# sherlock_anderson.net
KiCad netlist of a schematic drawn in EAGLE
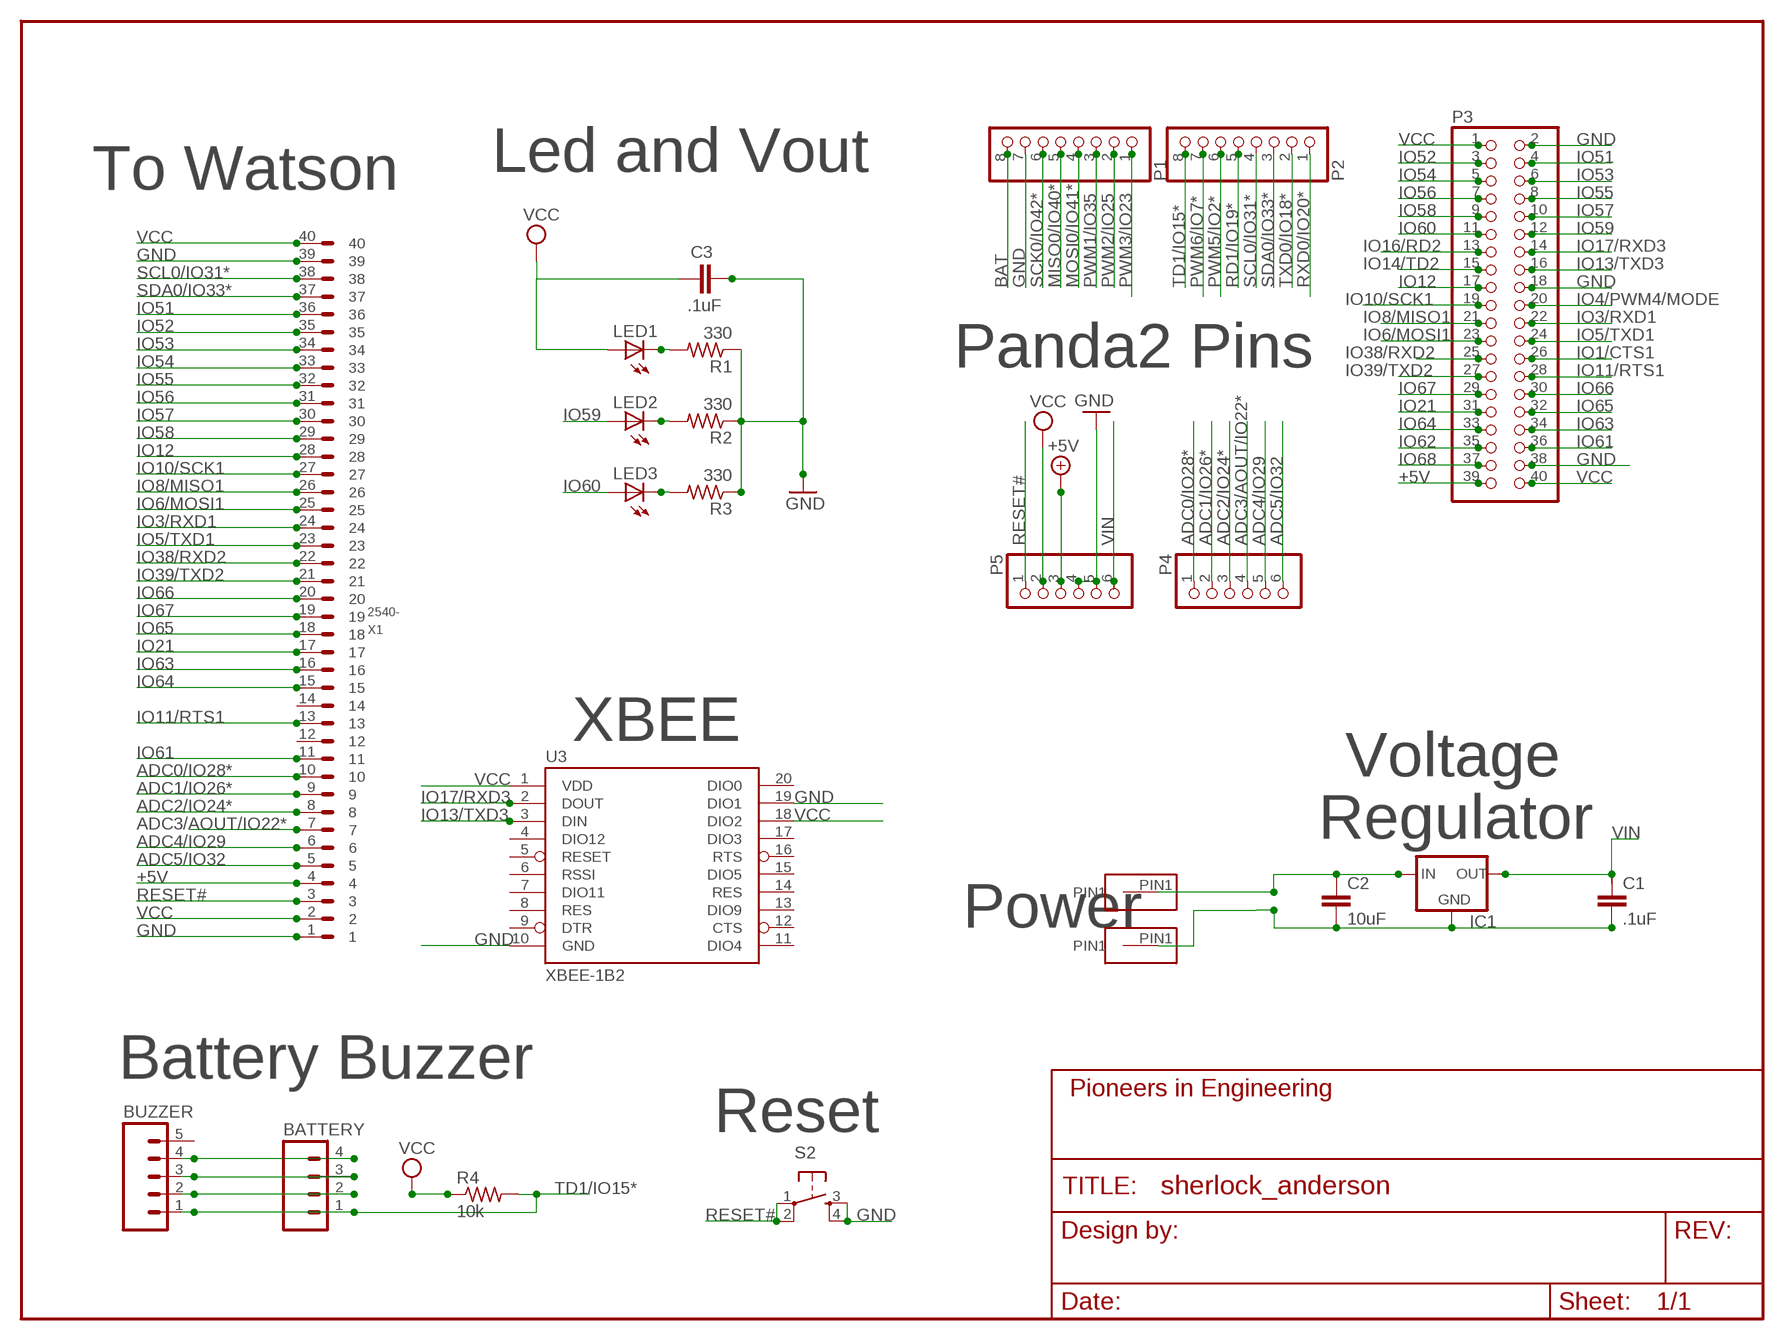
[diagram p0: schematic, sheet 1]

(export (version "E")
  (design (tool "Eeschema 10.0.6"))
  (components
    (comp (ref "BATTERY")
      (value "M041X04-MTA")
      (footprint "eagle-import:1X04-MTA")
      (fields (field (name "PARTNUMBER") "A1922-ND"))
      (libsource (lib "eagle-import") (part "M041X04-MTA"))
    )
    (comp (ref "BUZZER")
      (value "M05PTH")
      (footprint "eagle-import:1X05")
      (fields (field (name "PARTNUMBER") "965"))
      (libsource (lib "eagle-import") (part "M05PTH"))
    )
    (comp (ref "C1")
      (value ".1uF")
      (footprint "eagle-import:0603-CAP")
      (libsource (lib "eagle-import") (part "CAP0603-CAP"))
    )
    (comp (ref "C2")
      (value "10uF")
      (footprint "eagle-import:0603-CAP")
      (libsource (lib "eagle-import") (part "CAP0603-CAP"))
    )
    (comp (ref "C3")
      (value ".1uF")
      (footprint "eagle-import:0603-CAP")
      (libsource (lib "eagle-import") (part "CAP0603-CAP"))
    )
    (comp (ref "IC1")
      (value "V_REG_78XXSIDE")
      (footprint "eagle-import:78XXL")
      (fields (field (name "PARTNUMBER") "497-1446-5-ND"))
      (libsource (lib "eagle-import") (part "V_REG_78XXSIDE"))
    )
    (comp (ref "LED1")
      (value "LED0805")
      (footprint "eagle-import:LED-0805")
      (libsource (lib "eagle-import") (part "LED0805"))
    )
    (comp (ref "LED2")
      (value "LED0805")
      (footprint "eagle-import:LED-0805")
      (libsource (lib "eagle-import") (part "LED0805"))
    )
    (comp (ref "LED3")
      (value "LED0805")
      (footprint "eagle-import:LED-0805")
      (libsource (lib "eagle-import") (part "LED0805"))
    )
    (comp (ref "P1")
      (value "PINHD-1X8")
      (footprint "eagle-import:1X08")
      (fields (field (name "PARTNUMBER") "965"))
      (libsource (lib "eagle-import") (part "PINHD-1X8"))
    )
    (comp (ref "P2")
      (value "PINHD-1X8")
      (footprint "eagle-import:1X08")
      (fields (field (name "PARTNUMBER") "965"))
      (libsource (lib "eagle-import") (part "PINHD-1X8"))
    )
    (comp (ref "P3")
      (value "PINHD-2X20")
      (footprint "eagle-import:2X20")
      (fields (field (name "PARTNUMBER") "966"))
      (libsource (lib "eagle-import") (part "PINHD-2X20"))
    )
    (comp (ref "P4")
      (value "PINHD-1X6")
      (footprint "eagle-import:1X06")
      (fields (field (name "PARTNUMBER") "965"))
      (libsource (lib "eagle-import") (part "PINHD-1X6"))
    )
    (comp (ref "P5")
      (value "PINHD-1X6")
      (footprint "eagle-import:1X06")
      (fields (field (name "PARTNUMBER") "965"))
      (libsource (lib "eagle-import") (part "PINHD-1X6"))
    )
    (comp (ref "R1")
      (value "330")
      (footprint "eagle-import:R0603")
      (libsource (lib "eagle-import") (part "R-US_R0603"))
    )
    (comp (ref "R2")
      (value "330")
      (footprint "eagle-import:R0603")
      (libsource (lib "eagle-import") (part "R-US_R0603"))
    )
    (comp (ref "R3")
      (value "330")
      (footprint "eagle-import:R0603")
      (libsource (lib "eagle-import") (part "R-US_R0603"))
    )
    (comp (ref "R4")
      (value "10k")
      (footprint "eagle-import:R0603")
      (libsource (lib "eagle-import") (part "R-US_R0603"))
    )
    (comp (ref "S2")
      (value "TAC_SWITCHPTH")
      (footprint "eagle-import:TACTILE-PTH")
      (fields (field (name "PARTNUMBER") "S5751-10-ND"))
      (libsource (lib "eagle-import") (part "TAC_SWITCHPTH"))
    )
    (comp (ref "U$1")
      (value "ANDERSON_RA_BOTTOM")
      (footprint "eagle-import:ANDERSON_RA_BOTTOM")
      (libsource (lib "eagle-import") (part "ANDERSON_RA_BOTTOM"))
    )
    (comp (ref "U$5")
      (value "ANDERSON_RA_BOTTOM")
      (footprint "eagle-import:ANDERSON_RA_BOTTOM")
      (libsource (lib "eagle-import") (part "ANDERSON_RA_BOTTOM"))
    )
    (comp (ref "U3")
      (value "XBEE-1B2")
      (footprint "eagle-import:XBEE-SILK")
      (fields (field (name "PARTNUMBER") "S5751-10-ND"))
      (libsource (lib "eagle-import") (part "XBEE-1B2"))
    )
    (comp (ref "X1")
      (value "2540-")
      (footprint "eagle-import:PAK100_2500-40")
      (fields (field (name "PARTNUMBER") "S9175-ND"))
      (libsource (lib "eagle-import") (part "2540-"))
    )
  )
  (nets
    (net (code "1") (name "+5V") (class "Default")
      (node (ref "P3") (pin "39") (pinfunction "39_39") (pintype "passive"))
      (node (ref "P5") (pin "3") (pinfunction "3_3") (pintype "passive"))
      (node (ref "X1") (pin "4") (pinfunction "4_4") (pintype "bidirectional"))
    )
    (net (code "2") (name "/ADC0{slash}IO28*") (class "Default")
      (node (ref "P4") (pin "1") (pinfunction "1_1") (pintype "passive"))
      (node (ref "X1") (pin "10") (pinfunction "10_10") (pintype "bidirectional"))
    )
    (net (code "3") (name "/ADC1{slash}IO26*") (class "Default")
      (node (ref "P4") (pin "2") (pinfunction "2_2") (pintype "passive"))
      (node (ref "X1") (pin "9") (pinfunction "9_9") (pintype "bidirectional"))
    )
    (net (code "4") (name "/ADC2{slash}IO24*") (class "Default")
      (node (ref "P4") (pin "3") (pinfunction "3_3") (pintype "passive"))
      (node (ref "X1") (pin "8") (pinfunction "8_8") (pintype "bidirectional"))
    )
    (net (code "5") (name "/ADC3{slash}AOUT{slash}IO22*") (class "Default")
      (node (ref "P4") (pin "4") (pinfunction "4_4") (pintype "passive"))
      (node (ref "X1") (pin "7") (pinfunction "7_7") (pintype "bidirectional"))
    )
    (net (code "6") (name "/ADC4{slash}IO29") (class "Default")
      (node (ref "P4") (pin "5") (pinfunction "5_5") (pintype "passive"))
      (node (ref "X1") (pin "6") (pinfunction "6_6") (pintype "bidirectional"))
    )
    (net (code "7") (name "/ADC5{slash}IO32") (class "Default")
      (node (ref "P4") (pin "6") (pinfunction "6_6") (pintype "passive"))
      (node (ref "X1") (pin "5") (pinfunction "5_5") (pintype "bidirectional"))
    )
    (net (code "8") (name "/BAT") (class "Default")
      (node (ref "P1") (pin "8") (pinfunction "8_8") (pintype "passive"))
    )
    (net (code "9") (name "/IO1{slash}CTS1") (class "Default")
      (node (ref "P3") (pin "26") (pinfunction "26_26") (pintype "passive"))
    )
    (net (code "10") (name "/IO3{slash}RXD1") (class "Default")
      (node (ref "P3") (pin "22") (pinfunction "22_22") (pintype "passive"))
      (node (ref "X1") (pin "24") (pinfunction "24_24") (pintype "bidirectional"))
    )
    (net (code "11") (name "/IO4{slash}PWM4{slash}MODE") (class "Default")
      (node (ref "P3") (pin "20") (pinfunction "20_20") (pintype "passive"))
    )
    (net (code "12") (name "/IO5{slash}TXD1") (class "Default")
      (node (ref "P3") (pin "24") (pinfunction "24_24") (pintype "passive"))
      (node (ref "X1") (pin "23") (pinfunction "23_23") (pintype "bidirectional"))
    )
    (net (code "13") (name "/IO6{slash}MOSI1") (class "Default")
      (node (ref "P3") (pin "23") (pinfunction "23_23") (pintype "passive"))
      (node (ref "X1") (pin "25") (pinfunction "25_25") (pintype "bidirectional"))
    )
    (net (code "14") (name "/IO8{slash}MISO1") (class "Default")
      (node (ref "P3") (pin "21") (pinfunction "21_21") (pintype "passive"))
      (node (ref "X1") (pin "26") (pinfunction "26_26") (pintype "bidirectional"))
    )
    (net (code "15") (name "/IO10{slash}SCK1") (class "Default")
      (node (ref "P3") (pin "19") (pinfunction "19_19") (pintype "passive"))
      (node (ref "X1") (pin "27") (pinfunction "27_27") (pintype "bidirectional"))
    )
    (net (code "16") (name "/IO11{slash}RTS1") (class "Default")
      (node (ref "P3") (pin "28") (pinfunction "28_28") (pintype "passive"))
      (node (ref "X1") (pin "13") (pinfunction "13_13") (pintype "bidirectional"))
    )
    (net (code "17") (name "/IO12") (class "Default")
      (node (ref "P3") (pin "17") (pinfunction "17_17") (pintype "passive"))
      (node (ref "X1") (pin "28") (pinfunction "28_28") (pintype "bidirectional"))
    )
    (net (code "18") (name "/IO13{slash}TXD3") (class "Default")
      (node (ref "P3") (pin "16") (pinfunction "16_16") (pintype "passive"))
      (node (ref "U3") (pin "3") (pinfunction "DIN_3") (pintype "input"))
    )
    (net (code "19") (name "/IO14{slash}TD2") (class "Default")
      (node (ref "P3") (pin "15") (pinfunction "15_15") (pintype "passive"))
    )
    (net (code "20") (name "/IO16{slash}RD2") (class "Default")
      (node (ref "P3") (pin "13") (pinfunction "13_13") (pintype "passive"))
    )
    (net (code "21") (name "/IO17{slash}RXD3") (class "Default")
      (node (ref "P3") (pin "14") (pinfunction "14_14") (pintype "passive"))
      (node (ref "U3") (pin "2") (pinfunction "DOUT_2") (pintype "output"))
    )
    (net (code "22") (name "/IO21") (class "Default")
      (node (ref "P3") (pin "31") (pinfunction "31_31") (pintype "passive"))
      (node (ref "X1") (pin "17") (pinfunction "17_17") (pintype "bidirectional"))
    )
    (net (code "23") (name "/IO38{slash}RXD2") (class "Default")
      (node (ref "P3") (pin "25") (pinfunction "25_25") (pintype "passive"))
      (node (ref "X1") (pin "22") (pinfunction "22_22") (pintype "bidirectional"))
    )
    (net (code "24") (name "/IO39{slash}TXD2") (class "Default")
      (node (ref "P3") (pin "27") (pinfunction "27_27") (pintype "passive"))
      (node (ref "X1") (pin "21") (pinfunction "21_21") (pintype "bidirectional"))
    )
    (net (code "25") (name "/IO51") (class "Default")
      (node (ref "P3") (pin "4") (pinfunction "4_4") (pintype "passive"))
      (node (ref "X1") (pin "36") (pinfunction "36_36") (pintype "bidirectional"))
    )
    (net (code "26") (name "/IO52") (class "Default")
      (node (ref "P3") (pin "3") (pinfunction "3_3") (pintype "passive"))
      (node (ref "X1") (pin "35") (pinfunction "35_35") (pintype "bidirectional"))
    )
    (net (code "27") (name "/IO53") (class "Default")
      (node (ref "P3") (pin "6") (pinfunction "6_6") (pintype "passive"))
      (node (ref "X1") (pin "34") (pinfunction "34_34") (pintype "bidirectional"))
    )
    (net (code "28") (name "/IO54") (class "Default")
      (node (ref "P3") (pin "5") (pinfunction "5_5") (pintype "passive"))
      (node (ref "X1") (pin "33") (pinfunction "33_33") (pintype "bidirectional"))
    )
    (net (code "29") (name "/IO55") (class "Default")
      (node (ref "P3") (pin "8") (pinfunction "8_8") (pintype "passive"))
      (node (ref "X1") (pin "32") (pinfunction "32_32") (pintype "bidirectional"))
    )
    (net (code "30") (name "/IO56") (class "Default")
      (node (ref "P3") (pin "7") (pinfunction "7_7") (pintype "passive"))
      (node (ref "X1") (pin "31") (pinfunction "31_31") (pintype "bidirectional"))
    )
    (net (code "31") (name "/IO57") (class "Default")
      (node (ref "P3") (pin "10") (pinfunction "10_10") (pintype "passive"))
      (node (ref "X1") (pin "30") (pinfunction "30_30") (pintype "bidirectional"))
    )
    (net (code "32") (name "/IO58") (class "Default")
      (node (ref "P3") (pin "9") (pinfunction "9_9") (pintype "passive"))
      (node (ref "X1") (pin "29") (pinfunction "29_29") (pintype "bidirectional"))
    )
    (net (code "33") (name "/IO59") (class "Default")
      (node (ref "LED2") (pin "A") (pinfunction "A_A") (pintype "passive"))
      (node (ref "P3") (pin "12") (pinfunction "12_12") (pintype "passive"))
    )
    (net (code "34") (name "/IO60") (class "Default")
      (node (ref "LED3") (pin "A") (pinfunction "A_A") (pintype "passive"))
      (node (ref "P3") (pin "11") (pinfunction "11_11") (pintype "passive"))
    )
    (net (code "35") (name "/IO61") (class "Default")
      (node (ref "P3") (pin "36") (pinfunction "36_36") (pintype "passive"))
      (node (ref "X1") (pin "11") (pinfunction "11_11") (pintype "bidirectional"))
    )
    (net (code "36") (name "/IO62") (class "Default")
      (node (ref "P3") (pin "35") (pinfunction "35_35") (pintype "passive"))
    )
    (net (code "37") (name "/IO63") (class "Default")
      (node (ref "P3") (pin "34") (pinfunction "34_34") (pintype "passive"))
      (node (ref "X1") (pin "16") (pinfunction "16_16") (pintype "bidirectional"))
    )
    (net (code "38") (name "/IO64") (class "Default")
      (node (ref "P3") (pin "33") (pinfunction "33_33") (pintype "passive"))
      (node (ref "X1") (pin "15") (pinfunction "15_15") (pintype "bidirectional"))
    )
    (net (code "39") (name "/IO65") (class "Default")
      (node (ref "P3") (pin "32") (pinfunction "32_32") (pintype "passive"))
      (node (ref "X1") (pin "18") (pinfunction "18_18") (pintype "bidirectional"))
    )
    (net (code "40") (name "/IO66") (class "Default")
      (node (ref "P3") (pin "30") (pinfunction "30_30") (pintype "passive"))
      (node (ref "X1") (pin "20") (pinfunction "20_20") (pintype "bidirectional"))
    )
    (net (code "41") (name "/IO67") (class "Default")
      (node (ref "P3") (pin "29") (pinfunction "29_29") (pintype "passive"))
      (node (ref "X1") (pin "19") (pinfunction "19_19") (pintype "bidirectional"))
    )
    (net (code "42") (name "/IO68") (class "Default")
      (node (ref "P3") (pin "37") (pinfunction "37_37") (pintype "passive"))
    )
    (net (code "43") (name "/MISO0{slash}IO40*") (class "Default")
      (node (ref "P1") (pin "5") (pinfunction "5_5") (pintype "passive"))
    )
    (net (code "44") (name "/MOSI0{slash}IO41*") (class "Default")
      (node (ref "P1") (pin "4") (pinfunction "4_4") (pintype "passive"))
    )
    (net (code "45") (name "/PWM1{slash}IO35") (class "Default")
      (node (ref "P1") (pin "3") (pinfunction "3_3") (pintype "passive"))
    )
    (net (code "46") (name "/PWM2{slash}IO25") (class "Default")
      (node (ref "P1") (pin "2") (pinfunction "2_2") (pintype "passive"))
    )
    (net (code "47") (name "/PWM3{slash}IO23") (class "Default")
      (node (ref "P1") (pin "1") (pinfunction "1_1") (pintype "passive"))
    )
    (net (code "48") (name "/PWM5{slash}IO2*") (class "Default")
      (node (ref "P2") (pin "6") (pinfunction "6_6") (pintype "passive"))
    )
    (net (code "49") (name "/PWM6{slash}IO7*") (class "Default")
      (node (ref "P2") (pin "7") (pinfunction "7_7") (pintype "passive"))
    )
    (net (code "50") (name "/RD1{slash}IO19*") (class "Default")
      (node (ref "P2") (pin "5") (pinfunction "5_5") (pintype "passive"))
    )
    (net (code "51") (name "/RESET#") (class "Default")
      (node (ref "P5") (pin "1") (pinfunction "1_1") (pintype "passive"))
      (node (ref "S2") (pin "1") (pinfunction "1_1") (pintype "passive"))
      (node (ref "S2") (pin "2") (pinfunction "2_2") (pintype "passive"))
      (node (ref "X1") (pin "3") (pinfunction "3_3") (pintype "bidirectional"))
    )
    (net (code "52") (name "/RXD0{slash}IO20*") (class "Default")
      (node (ref "P2") (pin "1") (pinfunction "1_1") (pintype "passive"))
    )
    (net (code "53") (name "/SCK0{slash}IO42*") (class "Default")
      (node (ref "P1") (pin "6") (pinfunction "6_6") (pintype "passive"))
    )
    (net (code "54") (name "/SCL0{slash}IO31*") (class "Default")
      (node (ref "P2") (pin "4") (pinfunction "4_4") (pintype "passive"))
      (node (ref "X1") (pin "38") (pinfunction "38_38") (pintype "bidirectional"))
    )
    (net (code "55") (name "/SDA0{slash}IO33*") (class "Default")
      (node (ref "P2") (pin "3") (pinfunction "3_3") (pintype "passive"))
      (node (ref "X1") (pin "37") (pinfunction "37_37") (pintype "bidirectional"))
    )
    (net (code "56") (name "/TD1{slash}IO15*") (class "Default")
      (node (ref "BATTERY") (pin "1") (pinfunction "1_1") (pintype "passive"))
      (node (ref "BUZZER") (pin "1") (pinfunction "1_1") (pintype "passive"))
      (node (ref "P2") (pin "8") (pinfunction "8_8") (pintype "passive"))
      (node (ref "R4") (pin "2") (pinfunction "2_2") (pintype "passive"))
    )
    (net (code "57") (name "/TXD0{slash}IO18*") (class "Default")
      (node (ref "P2") (pin "2") (pinfunction "2_2") (pintype "passive"))
    )
    (net (code "58") (name "/VIN") (class "Default")
      (node (ref "C1") (pin "1") (pinfunction "1_1") (pintype "passive"))
      (node (ref "IC1") (pin "OUT") (pinfunction "OUT_OUT") (pintype "output"))
      (node (ref "P5") (pin "6") (pinfunction "6_6") (pintype "passive"))
    )
    (net (code "59") (name "GND") (class "Default")
      (node (ref "C1") (pin "2") (pinfunction "2_2") (pintype "passive"))
      (node (ref "C2") (pin "2") (pinfunction "2_2") (pintype "passive"))
      (node (ref "C3") (pin "2") (pinfunction "2_2") (pintype "passive"))
      (node (ref "IC1") (pin "GND") (pinfunction "GND_GND") (pintype "input"))
      (node (ref "P1") (pin "7") (pinfunction "7_7") (pintype "passive"))
      (node (ref "P3") (pin "18") (pinfunction "18_18") (pintype "passive"))
      (node (ref "P3") (pin "2") (pinfunction "2_2") (pintype "passive"))
      (node (ref "P3") (pin "38") (pinfunction "38_38") (pintype "passive"))
      (node (ref "P5") (pin "4") (pinfunction "4_4") (pintype "passive"))
      (node (ref "P5") (pin "5") (pinfunction "5_5") (pintype "passive"))
      (node (ref "R1") (pin "1") (pinfunction "1_1") (pintype "passive"))
      (node (ref "R2") (pin "1") (pinfunction "1_1") (pintype "passive"))
      (node (ref "R3") (pin "1") (pinfunction "1_1") (pintype "passive"))
      (node (ref "S2") (pin "3") (pinfunction "3_3") (pintype "passive"))
      (node (ref "S2") (pin "4") (pinfunction "4_4") (pintype "passive"))
      (node (ref "U$5") (pin "PIN1") (pinfunction "PIN1_PIN1") (pintype "bidirectional"))
      (node (ref "U3") (pin "10") (pinfunction "GND_10") (pintype "power_in"))
      (node (ref "U3") (pin "19") (pinfunction "DIO1_19") (pintype "bidirectional"))
      (node (ref "X1") (pin "1") (pinfunction "1_1") (pintype "bidirectional"))
      (node (ref "X1") (pin "39") (pinfunction "39_39") (pintype "bidirectional"))
    )
    (net (code "60") (name "Net-(BATTERY-Pad2)") (class "Default")
      (node (ref "BATTERY") (pin "2") (pinfunction "2_2") (pintype "passive"))
      (node (ref "BUZZER") (pin "2") (pinfunction "2_2") (pintype "passive"))
    )
    (net (code "61") (name "Net-(BATTERY-Pad3)") (class "Default")
      (node (ref "BATTERY") (pin "3") (pinfunction "3_3") (pintype "passive"))
      (node (ref "BUZZER") (pin "3") (pinfunction "3_3") (pintype "passive"))
    )
    (net (code "62") (name "Net-(BATTERY-Pad4)") (class "Default")
      (node (ref "BATTERY") (pin "4") (pinfunction "4_4") (pintype "passive"))
      (node (ref "BUZZER") (pin "4") (pinfunction "4_4") (pintype "passive"))
    )
    (net (code "63") (name "Net-(C2-Pad1)") (class "Default")
      (node (ref "C2") (pin "1") (pinfunction "1_1") (pintype "passive"))
      (node (ref "IC1") (pin "IN") (pinfunction "IN_IN") (pintype "input"))
      (node (ref "U$1") (pin "PIN1") (pinfunction "PIN1_PIN1") (pintype "bidirectional"))
    )
    (net (code "64") (name "Net-(LED1-PadC)") (class "Default")
      (node (ref "LED1") (pin "C") (pinfunction "C_C") (pintype "passive"))
      (node (ref "R1") (pin "2") (pinfunction "2_2") (pintype "passive"))
    )
    (net (code "65") (name "Net-(LED2-PadC)") (class "Default")
      (node (ref "LED2") (pin "C") (pinfunction "C_C") (pintype "passive"))
      (node (ref "R2") (pin "2") (pinfunction "2_2") (pintype "passive"))
    )
    (net (code "66") (name "Net-(LED3-PadC)") (class "Default")
      (node (ref "LED3") (pin "C") (pinfunction "C_C") (pintype "passive"))
      (node (ref "R3") (pin "2") (pinfunction "2_2") (pintype "passive"))
    )
    (net (code "67") (name "VCC") (class "Default")
      (node (ref "C3") (pin "1") (pinfunction "1_1") (pintype "passive"))
      (node (ref "LED1") (pin "A") (pinfunction "A_A") (pintype "passive"))
      (node (ref "P3") (pin "1") (pinfunction "1_1") (pintype "passive"))
      (node (ref "P3") (pin "40") (pinfunction "40_40") (pintype "passive"))
      (node (ref "P5") (pin "2") (pinfunction "2_2") (pintype "passive"))
      (node (ref "R4") (pin "1") (pinfunction "1_1") (pintype "passive"))
      (node (ref "U3") (pin "1") (pinfunction "VDD_1") (pintype "power_in"))
      (node (ref "U3") (pin "18") (pinfunction "DIO2_18") (pintype "bidirectional"))
      (node (ref "X1") (pin "2") (pinfunction "2_2") (pintype "bidirectional"))
      (node (ref "X1") (pin "40") (pinfunction "40_40") (pintype "bidirectional"))
    )
    (net (code "68") (name "unconnected-(BUZZER-Pad5)") (class "Default")
      (node (ref "BUZZER") (pin "5") (pinfunction "5_5") (pintype "passive"))
    )
    (net (code "69") (name "unconnected-(U3-CTS-Pad12)") (class "Default")
      (node (ref "U3") (pin "12") (pinfunction "CTS_12") (pintype "output"))
    )
    (net (code "70") (name "unconnected-(U3-DIO0-Pad20)") (class "Default")
      (node (ref "U3") (pin "20") (pinfunction "DIO0_20") (pintype "bidirectional"))
    )
    (net (code "71") (name "unconnected-(U3-DIO3-Pad17)") (class "Default")
      (node (ref "U3") (pin "17") (pinfunction "DIO3_17") (pintype "bidirectional"))
    )
    (net (code "72") (name "unconnected-(U3-DIO4-Pad11)") (class "Default")
      (node (ref "U3") (pin "11") (pinfunction "DIO4_11") (pintype "bidirectional"))
    )
    (net (code "73") (name "unconnected-(U3-DIO5-Pad15)") (class "Default")
      (node (ref "U3") (pin "15") (pinfunction "DIO5_15") (pintype "bidirectional"))
    )
    (net (code "74") (name "unconnected-(U3-DIO9-Pad13)") (class "Default")
      (node (ref "U3") (pin "13") (pinfunction "DIO9_13") (pintype "bidirectional"))
    )
    (net (code "75") (name "unconnected-(U3-DIO11-Pad7)") (class "Default")
      (node (ref "U3") (pin "7") (pinfunction "DIO11_7") (pintype "bidirectional"))
    )
    (net (code "76") (name "unconnected-(U3-DIO12-Pad4)") (class "Default")
      (node (ref "U3") (pin "4") (pinfunction "DIO12_4") (pintype "bidirectional"))
    )
    (net (code "77") (name "unconnected-(U3-DTR-Pad9)") (class "Default")
      (node (ref "U3") (pin "9") (pinfunction "DTR_9") (pintype "bidirectional"))
    )
    (net (code "78") (name "unconnected-(U3-RES-Pad8)") (class "Default")
      (node (ref "U3") (pin "8") (pinfunction "RES_8") (pintype "bidirectional"))
    )
    (net (code "79") (name "unconnected-(U3-RES-Pad14)") (class "Default")
      (node (ref "U3") (pin "14") (pinfunction "RES_14") (pintype "bidirectional"))
    )
    (net (code "80") (name "unconnected-(U3-RESET-Pad5)") (class "Default")
      (node (ref "U3") (pin "5") (pinfunction "RESET_5") (pintype "input"))
    )
    (net (code "81") (name "unconnected-(U3-RSSI-Pad6)") (class "Default")
      (node (ref "U3") (pin "6") (pinfunction "RSSI_6") (pintype "bidirectional"))
    )
    (net (code "82") (name "unconnected-(U3-RTS-Pad16)") (class "Default")
      (node (ref "U3") (pin "16") (pinfunction "RTS_16") (pintype "input"))
    )
    (net (code "83") (name "unconnected-(X1-Pad12)") (class "Default")
      (node (ref "X1") (pin "12") (pinfunction "12_12") (pintype "bidirectional"))
    )
    (net (code "84") (name "unconnected-(X1-Pad14)") (class "Default")
      (node (ref "X1") (pin "14") (pinfunction "14_14") (pintype "bidirectional"))
    )
  )
)
